# Ux.net
KiCad netlist of a schematic drawn in Altium Designer
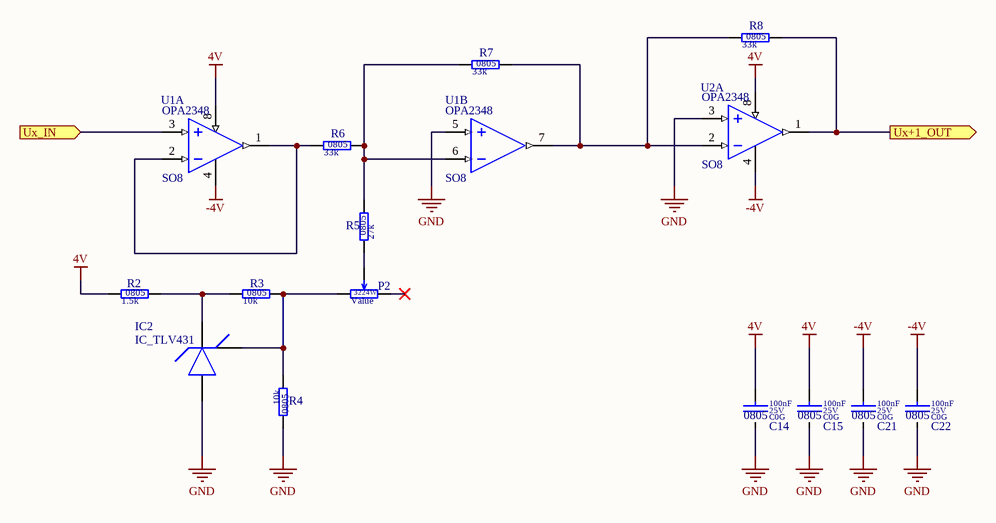
[diagram p0: Ux.SchDoc]

(export (version "E")
  (design (tool "Eeschema 10.0.6"))
  (components
    (comp (ref "C14")
      (value "100nF")
      (footprint "C_0805_2012")
      (description "Capacitor")
      (fields
        (field (name "DIELECTRIC") "C0G")
        (field (name "VOLTAGE") "25V")
        (field (name "SCH_FOOTPRINT") "0805")
        (field (name "Comment") "C_100nF_0805_C0G_25V_5")
      )
      (libsource (lib "SIUE_Symbol") (part "C_100nF_0805_C0G_25V_5"))
    )
    (comp (ref "C15")
      (value "100nF")
      (footprint "C_0805_2012")
      (description "Capacitor")
      (fields
        (field (name "DIELECTRIC") "C0G")
        (field (name "VOLTAGE") "25V")
        (field (name "SCH_FOOTPRINT") "0805")
        (field (name "Comment") "C_100nF_0805_C0G_25V_5")
      )
      (libsource (lib "SIUE_Symbol") (part "C_100nF_0805_C0G_25V_5"))
    )
    (comp (ref "C21")
      (value "100nF")
      (footprint "C_0805_2012")
      (description "Capacitor")
      (fields
        (field (name "DIELECTRIC") "C0G")
        (field (name "VOLTAGE") "25V")
        (field (name "SCH_FOOTPRINT") "0805")
        (field (name "Comment") "C_100nF_0805_C0G_25V_5")
      )
      (libsource (lib "SIUE_Symbol") (part "C_100nF_0805_C0G_25V_5"))
    )
    (comp (ref "C22")
      (value "100nF")
      (footprint "C_0805_2012")
      (description "Capacitor")
      (fields
        (field (name "DIELECTRIC") "C0G")
        (field (name "VOLTAGE") "25V")
        (field (name "SCH_FOOTPRINT") "0805")
        (field (name "Comment") "C_100nF_0805_C0G_25V_5")
      )
      (libsource (lib "SIUE_Symbol") (part "C_100nF_0805_C0G_25V_5"))
    )
    (comp (ref "IC2")
      (value "IC_TLV431")
      (footprint "SOT23")
      (libsource (lib "SIUE_Symbol") (part "IC_TLV431"))
    )
    (comp (ref "P2")
      (value "Value")
      (footprint "Potentiometer")
      (fields (field (name "SCH_FOOTPRINT") "3224W") (field (name "Comment") "POT"))
      (libsource (lib "SIUE_Symbol") (part "POT"))
    )
    (comp (ref "R2")
      (value "R_1.5k_0805_5_1")
      (footprint "R_0805_2012")
      (fields
        (field (name "TOLERANCE") "5")
        (field (name "SCH_FOOTPRINT") "0805")
        (field (name "RESISTANCE") "1.5k")
      )
      (libsource (lib "SIUE_Symbol") (part "R_1.5k_0805_5_1"))
    )
    (comp (ref "R3")
      (value "R_10k_0805_5")
      (footprint "R_0805_2012")
      (fields
        (field (name "TOLERANCE") "5")
        (field (name "SCH_FOOTPRINT") "0805")
        (field (name "RESISTANCE") "10k")
      )
      (libsource (lib "SIUE_Symbol") (part "R_10k_0805_5"))
    )
    (comp (ref "R4")
      (value "R_10k_0805_5")
      (footprint "R_0805_2012")
      (fields
        (field (name "TOLERANCE") "5")
        (field (name "SCH_FOOTPRINT") "0805")
        (field (name "RESISTANCE") "10k")
      )
      (libsource (lib "SIUE_Symbol") (part "R_10k_0805_5"))
    )
    (comp (ref "R5")
      (value "R_27k_0805_5")
      (footprint "R_0805_2012")
      (fields
        (field (name "TOLERANCE") "5")
        (field (name "SCH_FOOTPRINT") "0805")
        (field (name "RESISTANCE") "27k")
      )
      (libsource (lib "SIUE_Symbol") (part "R_27k_0805_5"))
    )
    (comp (ref "R6")
      (value "R_33k_0805_5")
      (footprint "R_0805_2012")
      (fields
        (field (name "TOLERANCE") "5")
        (field (name "SCH_FOOTPRINT") "0805")
        (field (name "RESISTANCE") "33k")
      )
      (libsource (lib "SIUE_Symbol") (part "R_33k_0805_5"))
    )
    (comp (ref "R7")
      (value "R_33k_0805_5")
      (footprint "R_0805_2012")
      (fields
        (field (name "TOLERANCE") "5")
        (field (name "SCH_FOOTPRINT") "0805")
        (field (name "RESISTANCE") "33k")
      )
      (libsource (lib "SIUE_Symbol") (part "R_33k_0805_5"))
    )
    (comp (ref "R8")
      (value "R_33k_0805_5")
      (footprint "R_0805_2012")
      (fields
        (field (name "TOLERANCE") "5")
        (field (name "SCH_FOOTPRINT") "0805")
        (field (name "RESISTANCE") "33k")
      )
      (libsource (lib "SIUE_Symbol") (part "R_33k_0805_5"))
    )
    (comp (ref "U1")
      (value "OPA2348")
      (footprint "SO8")
      (fields (field (name "SCH_FOOTPRINT") "SO8") (field (name "Comment") "A2_OPA2348"))
      (libsource (lib "SIUE_Symbol") (part "A2_OPA2348"))
    )
    (comp (ref "U2")
      (value "OPA2348")
      (footprint "SO8")
      (fields (field (name "SCH_FOOTPRINT") "SO8") (field (name "Comment") "A2_OPA2348"))
      (libsource (lib "SIUE_Symbol") (part "A2_OPA2348"))
    )
  )
  (nets
    (net (code "1") (name "-4V") (class "Default")
      (node (ref "C21") (pin "1") (pinfunction "1_1") (pintype "passive"))
      (node (ref "C22") (pin "1") (pinfunction "1_1") (pintype "passive"))
      (node (ref "U1") (pin "4") (pinfunction "GND_4") (pintype "power_in"))
      (node (ref "U2") (pin "4") (pinfunction "GND_4") (pintype "power_in"))
    )
    (net (code "2") (name "/Ux+1_OUT") (class "Default")
      (node (ref "R8") (pin "2") (pinfunction "2_2") (pintype "passive"))
      (node (ref "U2") (pin "1") (pinfunction "OUT1_1") (pintype "output"))
    )
    (net (code "3") (name "/Ux_IN") (class "Default")
      (node (ref "U1") (pin "3") (pinfunction "IN+1_3") (pintype "input"))
    )
    (net (code "4") (name "4V") (class "Default")
      (node (ref "C14") (pin "1") (pinfunction "1_1") (pintype "passive"))
      (node (ref "C15") (pin "1") (pinfunction "1_1") (pintype "passive"))
      (node (ref "R2") (pin "1") (pinfunction "1_1") (pintype "passive"))
      (node (ref "U1") (pin "8") (pinfunction "VDD_8") (pintype "input"))
      (node (ref "U2") (pin "8") (pinfunction "VDD_8") (pintype "input"))
    )
    (net (code "5") (name "GND") (class "Default")
      (node (ref "C14") (pin "2") (pinfunction "2_2") (pintype "passive"))
      (node (ref "C15") (pin "2") (pinfunction "2_2") (pintype "passive"))
      (node (ref "C21") (pin "2") (pinfunction "2_2") (pintype "passive"))
      (node (ref "C22") (pin "2") (pinfunction "2_2") (pintype "passive"))
      (node (ref "IC2") (pin "3") (pinfunction "ANODE_3") (pintype "passive"))
      (node (ref "R4") (pin "2") (pinfunction "2_2") (pintype "passive"))
      (node (ref "U1") (pin "5") (pinfunction "IN+2_5") (pintype "input"))
      (node (ref "U2") (pin "3") (pinfunction "IN+1_3") (pintype "input"))
    )
    (net (code "6") (name "Net-(IC2-CATH)") (class "Default")
      (node (ref "IC2") (pin "2") (pinfunction "CATH_2") (pintype "passive"))
      (node (ref "R2") (pin "2") (pinfunction "2_2") (pintype "passive"))
      (node (ref "R3") (pin "1") (pinfunction "1_1") (pintype "passive"))
    )
    (net (code "7") (name "Net-(IC2-REF)") (class "Default")
      (node (ref "IC2") (pin "1") (pinfunction "REF_1") (pintype "passive"))
      (node (ref "P2") (pin "1") (pinfunction "1_1") (pintype "passive"))
      (node (ref "R3") (pin "2") (pinfunction "2_2") (pintype "passive"))
      (node (ref "R4") (pin "1") (pinfunction "1_1") (pintype "passive"))
    )
    (net (code "8") (name "Net-(P2-Pad2)") (class "Default")
      (node (ref "P2") (pin "2") (pinfunction "2_2") (pintype "passive"))
      (node (ref "R5") (pin "1") (pinfunction "1_1") (pintype "passive"))
    )
    (net (code "9") (name "Net-(U1A-IN-1)") (class "Default")
      (node (ref "R6") (pin "1") (pinfunction "1_1") (pintype "passive"))
      (node (ref "U1") (pin "1") (pinfunction "OUT1_1") (pintype "output"))
      (node (ref "U1") (pin "2") (pinfunction "IN-1_2") (pintype "input"))
    )
    (net (code "10") (name "Net-(U1B-IN-2)") (class "Default")
      (node (ref "R5") (pin "2") (pinfunction "2_2") (pintype "passive"))
      (node (ref "R6") (pin "2") (pinfunction "2_2") (pintype "passive"))
      (node (ref "R7") (pin "1") (pinfunction "1_1") (pintype "passive"))
      (node (ref "U1") (pin "6") (pinfunction "IN-2_6") (pintype "input"))
    )
    (net (code "11") (name "Net-(U1B-OUT2)") (class "Default")
      (node (ref "R7") (pin "2") (pinfunction "2_2") (pintype "passive"))
      (node (ref "R8") (pin "1") (pinfunction "1_1") (pintype "passive"))
      (node (ref "U1") (pin "7") (pinfunction "OUT2_7") (pintype "output"))
      (node (ref "U2") (pin "2") (pinfunction "IN-1_2") (pintype "input"))
    )
    (net (code "12") (name "unconnected-(P2-Pad3)") (class "Default")
      (node (ref "P2") (pin "3") (pinfunction "3_3") (pintype "passive+no_connect"))
    )
  )
)
